# Serial.net
KiCad netlist of a schematic drawn in Altium Designer
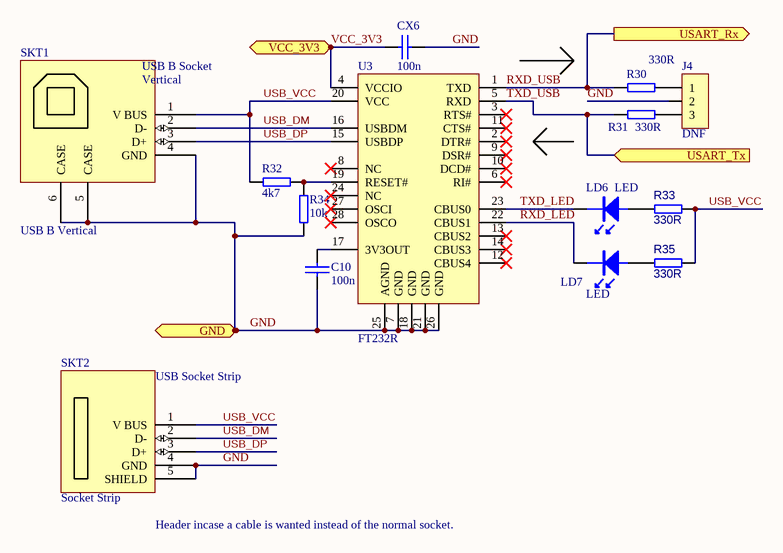
[diagram p0: Serial.SchDoc]

(export (version "E")
  (design (tool "Eeschema 10.0.6"))
  (components
    (comp (ref "C10") (value "100n") (footprint "0603") (libsource (lib "*") (part "CAP")))
    (comp (ref "CX6") (value "100n") (footprint "0603") (libsource (lib "*") (part "CAP")))
    (comp (ref "J4") (value "DNF") (footprint "sip3") (libsource (lib "DEVICE") (part "CON3")))
    (comp (ref "LD6") (value "LED") (footprint "LED3") (libsource (lib "DEVICE") (part "LED")))
    (comp (ref "LD7") (value "LED") (footprint "LED3") (libsource (lib "DEVICE") (part "LED")))
    (comp (ref "R30") (value "330R") (footprint "0603") (libsource (lib "DEVICE") (part "RES8")))
    (comp (ref "R31") (value "330R") (footprint "0603") (libsource (lib "DEVICE") (part "RES8")))
    (comp (ref "R32") (value "4k7") (footprint "0603") (libsource (lib "DEVICE") (part "RES8")))
    (comp (ref "R33") (value "330R") (footprint "0603") (libsource (lib "DEVICE") (part "RES8")))
    (comp (ref "R34") (value "10k") (footprint "0603") (libsource (lib "DEVICE") (part "RES8")))
    (comp (ref "R35") (value "330R") (footprint "0603") (libsource (lib "DEVICE") (part "RES8")))
    (comp (ref "SKT1")
      (value "USB B Vertical")
      (footprint "USB_B_Vertical")
      (libsource (lib "USB_Devices") (part "USB_B_Vertical"))
    )
    (comp (ref "SKT2")
      (value "Socket Strip")
      (footprint "USB_SocketStrip")
      (libsource (lib "USB_Devices") (part "USB_Pins"))
    )
    (comp (ref "U3") (value "FT232R") (footprint "ssop28") (libsource (lib "FTDI") (part "FT232R")))
  )
  (nets
    (net (code "1") (name "/GND") (class "Default")
      (node (ref "C10") (pin "1") (pintype "passive"))
      (node (ref "CX6") (pin "1") (pintype "passive"))
      (node (ref "J4") (pin "2") (pinfunction "2_2") (pintype "passive"))
      (node (ref "R34") (pin "1") (pintype "passive"))
      (node (ref "SKT1") (pin "4") (pinfunction "GND_4") (pintype "power_in"))
      (node (ref "SKT1") (pin "5") (pinfunction "CASE_5") (pintype "power_in"))
      (node (ref "SKT1") (pin "6") (pinfunction "CASE_6") (pintype "power_in"))
      (node (ref "SKT2") (pin "4") (pinfunction "GND_4") (pintype "power_in"))
      (node (ref "SKT2") (pin "5") (pinfunction "SHIELD_5") (pintype "power_in"))
      (node (ref "U3") (pin "18") (pinfunction "GND_18") (pintype "passive"))
      (node (ref "U3") (pin "21") (pinfunction "GND_21") (pintype "passive"))
      (node (ref "U3") (pin "25") (pinfunction "AGND_25") (pintype "passive"))
      (node (ref "U3") (pin "26") (pinfunction "GND_26") (pintype "passive"))
      (node (ref "U3") (pin "7") (pinfunction "GND_7") (pintype "passive"))
    )
    (net (code "2") (name "/RXD_LED") (class "Default")
      (node (ref "LD7") (pin "K") (pintype "passive"))
      (node (ref "U3") (pin "22") (pinfunction "CBUS1_22") (pintype "passive"))
    )
    (net (code "3") (name "/RXD_USB") (class "Default")
      (node (ref "R30") (pin "2") (pintype "passive"))
      (node (ref "U3") (pin "1") (pinfunction "TXD_1") (pintype "passive"))
    )
    (net (code "4") (name "/TXD_LED") (class "Default")
      (node (ref "LD6") (pin "K") (pintype "passive"))
      (node (ref "U3") (pin "23") (pinfunction "CBUS0_23") (pintype "passive"))
    )
    (net (code "5") (name "/TXD_USB") (class "Default")
      (node (ref "R31") (pin "2") (pintype "passive"))
      (node (ref "U3") (pin "5") (pinfunction "RXD_5") (pintype "passive"))
    )
    (net (code "6") (name "/USB_DM") (class "Default")
      (node (ref "SKT1") (pin "2") (pinfunction "D-_2") (pintype "bidirectional"))
      (node (ref "SKT2") (pin "2") (pinfunction "D-_2") (pintype "bidirectional"))
      (node (ref "U3") (pin "16") (pinfunction "USBDM_16") (pintype "passive"))
    )
    (net (code "7") (name "/USB_DP") (class "Default")
      (node (ref "SKT1") (pin "3") (pinfunction "D+_3") (pintype "bidirectional"))
      (node (ref "SKT2") (pin "3") (pinfunction "D+_3") (pintype "bidirectional"))
      (node (ref "U3") (pin "15") (pinfunction "USBDP_15") (pintype "passive"))
    )
    (net (code "8") (name "/USB_VCC") (class "Default")
      (node (ref "R32") (pin "1") (pintype "passive"))
      (node (ref "R33") (pin "1") (pintype "passive"))
      (node (ref "R35") (pin "1") (pintype "passive"))
      (node (ref "SKT1") (pin "1") (pinfunction "V_BUS_1") (pintype "power_in"))
      (node (ref "SKT2") (pin "1") (pinfunction "V_BUS_1") (pintype "power_in"))
      (node (ref "U3") (pin "20") (pinfunction "VCC_20") (pintype "passive"))
    )
    (net (code "9") (name "/VCC_3V3") (class "Default")
      (node (ref "CX6") (pin "2") (pintype "passive"))
      (node (ref "U3") (pin "4") (pinfunction "VCCIO_4") (pintype "passive"))
    )
    (net (code "10") (name "Net-(J4-Pad1)") (class "Default")
      (node (ref "J4") (pin "1") (pinfunction "1_1") (pintype "passive"))
      (node (ref "R30") (pin "1") (pintype "passive"))
    )
    (net (code "11") (name "Net-(J4-Pad3)") (class "Default")
      (node (ref "J4") (pin "3") (pinfunction "3_3") (pintype "passive"))
      (node (ref "R31") (pin "1") (pintype "passive"))
    )
    (net (code "12") (name "Net-(LD6-PadA)") (class "Default")
      (node (ref "LD6") (pin "A") (pintype "passive"))
      (node (ref "R33") (pin "2") (pintype "passive"))
    )
    (net (code "13") (name "Net-(LD7-PadA)") (class "Default")
      (node (ref "LD7") (pin "A") (pintype "passive"))
      (node (ref "R35") (pin "2") (pintype "passive"))
    )
    (net (code "14") (name "Net-(U3-3V3OUT)") (class "Default")
      (node (ref "C10") (pin "2") (pintype "passive"))
      (node (ref "U3") (pin "17") (pinfunction "3V3OUT_17") (pintype "passive"))
    )
    (net (code "15") (name "Net-(U3-RESET#)") (class "Default")
      (node (ref "R32") (pin "2") (pintype "passive"))
      (node (ref "R34") (pin "2") (pintype "passive"))
      (node (ref "U3") (pin "19") (pinfunction "RESET#_19") (pintype "passive"))
    )
    (net (code "16") (name "unconnected-(U3-CBUS2-Pad13)") (class "Default")
      (node (ref "U3") (pin "13") (pinfunction "CBUS2_13") (pintype "passive+no_connect"))
    )
    (net (code "17") (name "unconnected-(U3-CBUS3-Pad14)") (class "Default")
      (node (ref "U3") (pin "14") (pinfunction "CBUS3_14") (pintype "passive+no_connect"))
    )
    (net (code "18") (name "unconnected-(U3-CBUS4-Pad12)") (class "Default")
      (node (ref "U3") (pin "12") (pinfunction "CBUS4_12") (pintype "passive+no_connect"))
    )
    (net (code "19") (name "unconnected-(U3-CTS#-Pad11)") (class "Default")
      (node (ref "U3") (pin "11") (pinfunction "CTS#_11") (pintype "passive+no_connect"))
    )
    (net (code "20") (name "unconnected-(U3-DCD#-Pad10)") (class "Default")
      (node (ref "U3") (pin "10") (pinfunction "DCD#_10") (pintype "passive+no_connect"))
    )
    (net (code "21") (name "unconnected-(U3-DSR#-Pad9)") (class "Default")
      (node (ref "U3") (pin "9") (pinfunction "DSR#_9") (pintype "passive+no_connect"))
    )
    (net (code "22") (name "unconnected-(U3-DTR#-Pad2)") (class "Default")
      (node (ref "U3") (pin "2") (pinfunction "DTR#_2") (pintype "passive+no_connect"))
    )
    (net (code "23") (name "unconnected-(U3-NC-Pad8)") (class "Default")
      (node (ref "U3") (pin "8") (pinfunction "NC_8") (pintype "passive+no_connect"))
    )
    (net (code "24") (name "unconnected-(U3-NC-Pad24)") (class "Default")
      (node (ref "U3") (pin "24") (pinfunction "NC_24") (pintype "passive+no_connect"))
    )
    (net (code "25") (name "unconnected-(U3-OSCI-Pad27)") (class "Default")
      (node (ref "U3") (pin "27") (pinfunction "OSCI_27") (pintype "passive+no_connect"))
    )
    (net (code "26") (name "unconnected-(U3-OSCO-Pad28)") (class "Default")
      (node (ref "U3") (pin "28") (pinfunction "OSCO_28") (pintype "passive+no_connect"))
    )
    (net (code "27") (name "unconnected-(U3-RI#-Pad6)") (class "Default")
      (node (ref "U3") (pin "6") (pinfunction "RI#_6") (pintype "passive+no_connect"))
    )
    (net (code "28") (name "unconnected-(U3-RTS#-Pad3)") (class "Default")
      (node (ref "U3") (pin "3") (pinfunction "RTS#_3") (pintype "passive+no_connect"))
    )
  )
)
